# v1_0.net
KiCad netlist of a schematic drawn in EAGLE
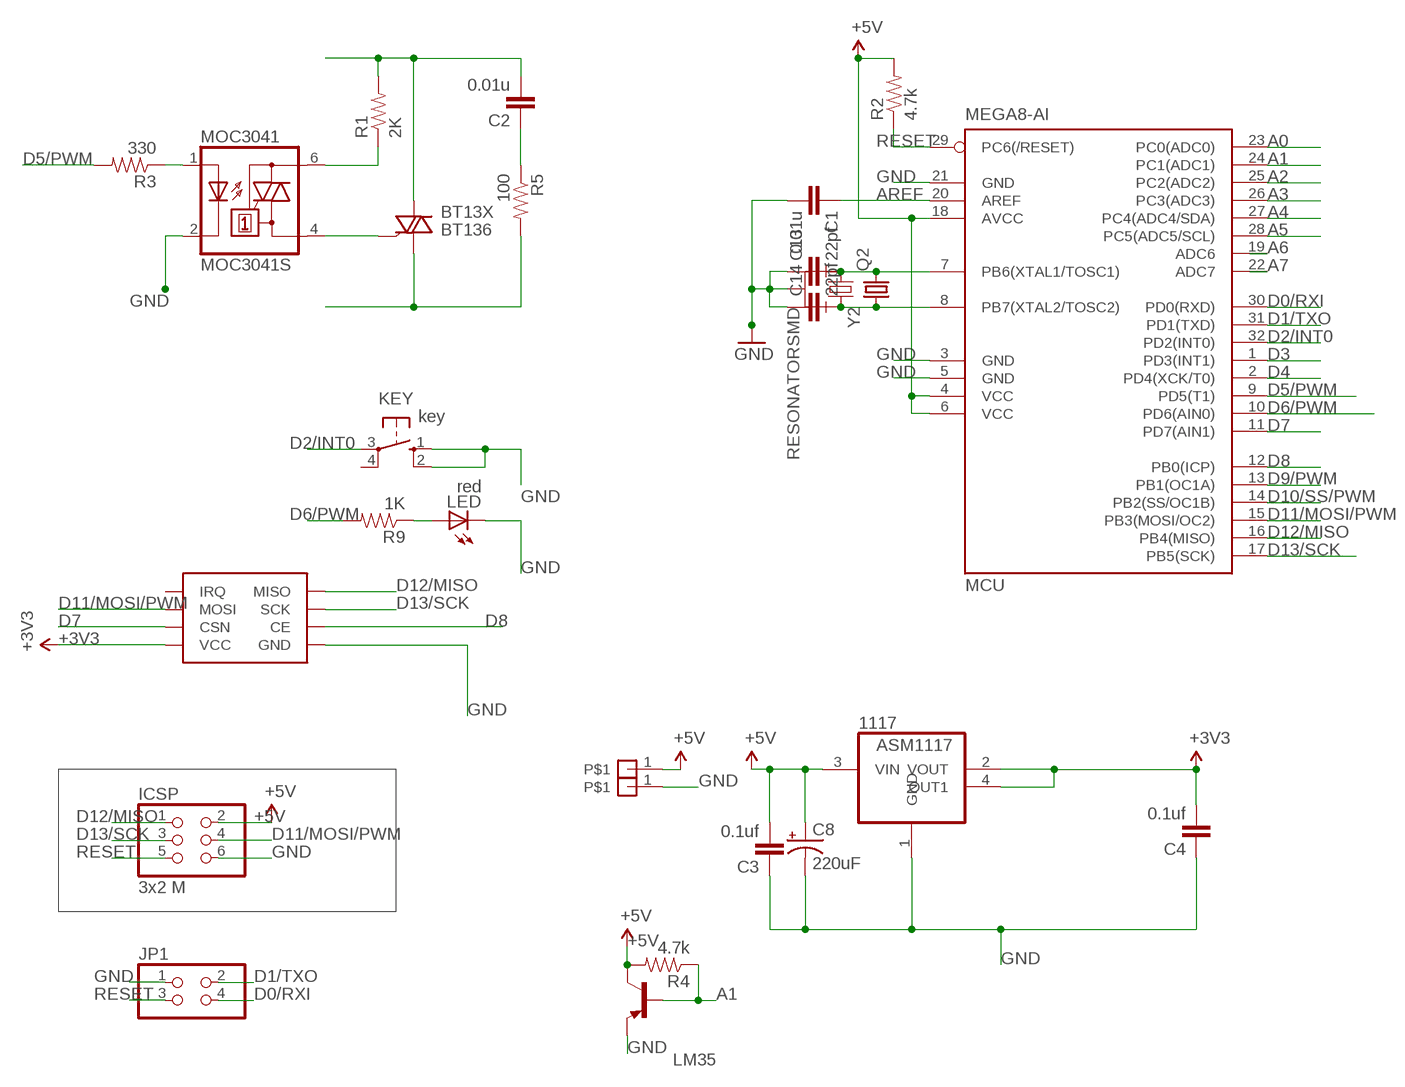
[diagram p0: schematic, sheet 1]

(export (version "E")
  (design (tool "Eeschema 10.0.6"))
  (components
    (comp (ref "1117")
      (value "ASM1117")
      (footprint "eagle-import:SOT223")
      (fields (field (name "MPN") "REG1117"))
      (libsource (lib "eagle-import") (part "ASM1117"))
    )
    (comp (ref "BT13X")
      (value "BT136")
      (footprint "eagle-import:TO252")
      (libsource (lib "eagle-import") (part "BT136"))
    )
    (comp (ref "C1")
      (value "0.01u")
      (footprint "eagle-import:0603-CAP")
      (libsource (lib "eagle-import") (part "MY2_CAP0603-CAP"))
    )
    (comp (ref "C2")
      (value "0.01u")
      (footprint "eagle-import:C050-024X044")
      (libsource (lib "eagle-import") (part "C-EU050-024X044"))
    )
    (comp (ref "C3")
      (value "0.1uf")
      (footprint "eagle-import:0603-CAP")
      (libsource (lib "eagle-import") (part "MY_CAP0603-CAP"))
    )
    (comp (ref "C4")
      (value "0.1uf")
      (footprint "eagle-import:0603-CAP")
      (libsource (lib "eagle-import") (part "MY_CAP0603-CAP"))
    )
    (comp (ref "C8")
      (value "220uF")
      (footprint "eagle-import:EIA3528")
      (libsource (lib "eagle-import") (part "CAP_POL3528"))
    )
    (comp (ref "C13")
      (value "22pf")
      (footprint "eagle-import:0603-CAP")
      (libsource (lib "eagle-import") (part "CAP0603-CAP"))
    )
    (comp (ref "C14")
      (value "22pf")
      (footprint "eagle-import:0603-CAP")
      (libsource (lib "eagle-import") (part "CAP0603-CAP"))
    )
    (comp (ref "ICSP")
      (value "3x2 M")
      (footprint "eagle-import:2X03")
      (libsource (lib "eagle-import") (part "PINHD-2X3"))
    )
    (comp (ref "JP1")
      (value "PINHD-2X2")
      (footprint "eagle-import:2X02")
      (libsource (lib "eagle-import") (part "PINHD-2X2"))
    )
    (comp (ref "KEY")
      (value "key")
      (footprint "eagle-import:B3F-10XX")
      (fields
        (field (name "MPN") "B3F-1000")
        (field (name "MPN_1") "B3F-1000")
        (field (name "OC_FARNELL") "176432")
        (field (name "OC_NEWARK") "36M3542")
      )
      (libsource (lib "eagle-import") (part "10-XX"))
    )
    (comp (ref "LED")
      (value "red")
      (footprint "eagle-import:LED3MM")
      (libsource (lib "eagle-import") (part "LED3MM"))
    )
    (comp (ref "LM35")
      (value "-PNP-TO92-E1")
      (footprint "eagle-import:TO92-E1")
      (libsource (lib "eagle-import") (part "-PNP-TO92-E1"))
    )
    (comp (ref "MCU")
      (value "MEGA8-AI")
      (footprint "eagle-import:TQFP32-08")
      (fields (field (name "MPN") "ATMEGA8-16AU"))
      (libsource (lib "eagle-import") (part "MEGA8-AI"))
    )
    (comp (ref "MOC3041")
      (value "MOC3041S")
      (footprint "eagle-import:DIL6-SMD")
      (fields
        (field (name "MF") "FAIRCHILD SEMICONDUCTOR")
        (field (name "MPN") "MOC3041S-M")
        (field (name "MF_1") "FAIRCHILD SEMICONDUCTOR")
        (field (name "MPN_1") "MOC3041S-M")
        (field (name "OC_NEWARK") "05C2885")
      )
      (libsource (lib "eagle-import") (part "MOC30S41"))
    )
    (comp (ref "Q2")
      (value "CRYSTALHC49S")
      (footprint "eagle-import:HC49_S")
      (libsource (lib "eagle-import") (part "CRYSTALHC49S"))
    )
    (comp (ref "R1")
      (value "2K")
      (footprint "eagle-import:AXIAL-0.3")
      (libsource (lib "eagle-import") (part "MY3_RESISTORPTH1"))
    )
    (comp (ref "R2")
      (value "4.7k")
      (footprint "eagle-import:0603-RES")
      (libsource (lib "eagle-import") (part "RESISTOR0603-RES"))
    )
    (comp (ref "R3")
      (value "330")
      (footprint "eagle-import:0603-RES")
      (libsource (lib "eagle-import") (part "RESISTOR0603-RES"))
    )
    (comp (ref "R4")
      (value "4.7k")
      (footprint "eagle-import:0603-RES")
      (libsource (lib "eagle-import") (part "RESISTOR0603-RES"))
    )
    (comp (ref "R5")
      (value "100")
      (footprint "eagle-import:AXIAL-0.3")
      (libsource (lib "eagle-import") (part "MY3_RESISTORPTH1"))
    )
    (comp (ref "R9")
      (value "1K")
      (footprint "eagle-import:0603-RES")
      (libsource (lib "eagle-import") (part "RESISTOR0603-RES"))
    )
    (comp (ref "U$3")
      (value "PIN1")
      (footprint "eagle-import:PIN1")
      (libsource (lib "eagle-import") (part "PIN1"))
    )
    (comp (ref "U$4")
      (value "PIN1")
      (footprint "eagle-import:PIN1")
      (libsource (lib "eagle-import") (part "PIN1"))
    )
    (comp (ref "U$6")
      (value "NRF")
      (footprint "eagle-import:NRF")
      (libsource (lib "eagle-import") (part "NRF"))
    )
    (comp (ref "Y2")
      (value "RESONATORSMD")
      (footprint "eagle-import:RESONATOR-SMD")
      (libsource (lib "eagle-import") (part "RESONATORSMD"))
    )
  )
  (nets
    (net (code "1") (name "+3V3") (class "Default")
      (node (ref "1117") (pin "2") (pinfunction "VOUT_2") (pintype "output"))
      (node (ref "1117") (pin "4") (pinfunction "OUT1_4") (pintype "bidirectional"))
      (node (ref "C4") (pin "2") (pinfunction "2_2") (pintype "passive"))
      (node (ref "U$6") (pin "P$2") (pinfunction "VCC_P$2") (pintype "bidirectional"))
    )
    (net (code "2") (name "+5V") (class "Default")
      (node (ref "1117") (pin "3") (pinfunction "VIN_3") (pintype "input"))
      (node (ref "C3") (pin "2") (pinfunction "2_2") (pintype "passive"))
      (node (ref "C8") (pin "A") (pinfunction "+_A") (pintype "passive"))
      (node (ref "ICSP") (pin "2") (pinfunction "2_2") (pintype "passive"))
      (node (ref "LM35") (pin "1") (pinfunction "C_1") (pintype "passive"))
      (node (ref "MCU") (pin "18") (pinfunction "AVCC_18") (pintype "power_in"))
      (node (ref "MCU") (pin "4") (pinfunction "VCC_4") (pintype "power_in"))
      (node (ref "MCU") (pin "6") (pinfunction "VCC_6") (pintype "power_in"))
      (node (ref "R2") (pin "2") (pinfunction "2_2") (pintype "passive"))
      (node (ref "R4") (pin "2") (pinfunction "2_2") (pintype "passive"))
      (node (ref "U$3") (pin "1") (pinfunction "P$1_1") (pintype "bidirectional"))
    )
    (net (code "3") (name "/A0") (class "Default")
      (node (ref "MCU") (pin "23") (pinfunction "PC0(ADC0)_23") (pintype "bidirectional"))
    )
    (net (code "4") (name "/A1") (class "Default")
      (node (ref "LM35") (pin "2") (pinfunction "B_2") (pintype "passive"))
      (node (ref "MCU") (pin "24") (pinfunction "PC1(ADC1)_24") (pintype "bidirectional"))
      (node (ref "R4") (pin "1") (pinfunction "1_1") (pintype "passive"))
    )
    (net (code "5") (name "/A2") (class "Default")
      (node (ref "MCU") (pin "25") (pinfunction "PC2(ADC2)_25") (pintype "bidirectional"))
    )
    (net (code "6") (name "/A3") (class "Default")
      (node (ref "MCU") (pin "26") (pinfunction "PC3(ADC3)_26") (pintype "bidirectional"))
    )
    (net (code "7") (name "/A4") (class "Default")
      (node (ref "MCU") (pin "27") (pinfunction "PC4(ADC4/SDA)_27") (pintype "bidirectional"))
    )
    (net (code "8") (name "/A5") (class "Default")
      (node (ref "MCU") (pin "28") (pinfunction "PC5(ADC5/SCL)_28") (pintype "bidirectional"))
    )
    (net (code "9") (name "/A6") (class "Default")
      (node (ref "MCU") (pin "19") (pinfunction "ADC6_19") (pintype "bidirectional"))
    )
    (net (code "10") (name "/A7") (class "Default")
      (node (ref "MCU") (pin "22") (pinfunction "ADC7_22") (pintype "bidirectional"))
    )
    (net (code "11") (name "/AREF") (class "Default")
      (node (ref "C1") (pin "1") (pinfunction "1_1") (pintype "passive"))
      (node (ref "MCU") (pin "20") (pinfunction "AREF_20") (pintype "passive"))
    )
    (net (code "12") (name "/D0{slash}RXI") (class "Default")
      (node (ref "JP1") (pin "4") (pinfunction "4_4") (pintype "passive"))
      (node (ref "MCU") (pin "30") (pinfunction "PD0(RXD)_30") (pintype "bidirectional"))
    )
    (net (code "13") (name "/D1{slash}TXO") (class "Default")
      (node (ref "JP1") (pin "2") (pinfunction "2_2") (pintype "passive"))
      (node (ref "MCU") (pin "31") (pinfunction "PD1(TXD)_31") (pintype "bidirectional"))
    )
    (net (code "14") (name "/D2{slash}INT0") (class "Default")
      (node (ref "KEY") (pin "3") (pinfunction "P_3") (pintype "passive"))
      (node (ref "MCU") (pin "32") (pinfunction "PD2(INT0)_32") (pintype "bidirectional"))
    )
    (net (code "15") (name "/D3") (class "Default")
      (node (ref "MCU") (pin "1") (pinfunction "PD3(INT1)_1") (pintype "bidirectional"))
    )
    (net (code "16") (name "/D4") (class "Default")
      (node (ref "MCU") (pin "2") (pinfunction "PD4(XCK/T0)_2") (pintype "bidirectional"))
    )
    (net (code "17") (name "/D5{slash}PWM") (class "Default")
      (node (ref "MCU") (pin "9") (pinfunction "PD5(T1)_9") (pintype "bidirectional"))
      (node (ref "R3") (pin "2") (pinfunction "2_2") (pintype "passive"))
    )
    (net (code "18") (name "/D6{slash}PWM") (class "Default")
      (node (ref "MCU") (pin "10") (pinfunction "PD6(AIN0)_10") (pintype "bidirectional"))
      (node (ref "R9") (pin "2") (pinfunction "2_2") (pintype "passive"))
    )
    (net (code "19") (name "/D7") (class "Default")
      (node (ref "MCU") (pin "11") (pinfunction "PD7(AIN1)_11") (pintype "bidirectional"))
      (node (ref "U$6") (pin "P$4") (pinfunction "CSN_P$4") (pintype "bidirectional"))
    )
    (net (code "20") (name "/D8") (class "Default")
      (node (ref "MCU") (pin "12") (pinfunction "PB0(ICP)_12") (pintype "bidirectional"))
      (node (ref "U$6") (pin "P$3") (pinfunction "CE_P$3") (pintype "bidirectional"))
    )
    (net (code "21") (name "/D9{slash}PWM") (class "Default")
      (node (ref "MCU") (pin "13") (pinfunction "PB1(OC1A)_13") (pintype "bidirectional"))
    )
    (net (code "22") (name "/D10{slash}SS{slash}PWM") (class "Default")
      (node (ref "MCU") (pin "14") (pinfunction "PB2(SS/OC1B)_14") (pintype "bidirectional"))
    )
    (net (code "23") (name "/D11{slash}MOSI{slash}PWM") (class "Default")
      (node (ref "ICSP") (pin "4") (pinfunction "4_4") (pintype "passive"))
      (node (ref "MCU") (pin "15") (pinfunction "PB3(MOSI/OC2)_15") (pintype "bidirectional"))
      (node (ref "U$6") (pin "P$6") (pinfunction "MOSI_P$6") (pintype "bidirectional"))
    )
    (net (code "24") (name "/D12{slash}MISO") (class "Default")
      (node (ref "ICSP") (pin "1") (pinfunction "1_1") (pintype "passive"))
      (node (ref "MCU") (pin "16") (pinfunction "PB4(MISO)_16") (pintype "bidirectional"))
      (node (ref "U$6") (pin "P$7") (pinfunction "MISO_P$7") (pintype "bidirectional"))
    )
    (net (code "25") (name "/D13{slash}SCK") (class "Default")
      (node (ref "ICSP") (pin "3") (pinfunction "3_3") (pintype "passive"))
      (node (ref "MCU") (pin "17") (pinfunction "PB5(SCK)_17") (pintype "bidirectional"))
      (node (ref "U$6") (pin "P$5") (pinfunction "SCK_P$5") (pintype "bidirectional"))
    )
    (net (code "26") (name "/RESET") (class "Default")
      (node (ref "ICSP") (pin "5") (pinfunction "5_5") (pintype "passive"))
      (node (ref "JP1") (pin "3") (pinfunction "3_3") (pintype "passive"))
      (node (ref "MCU") (pin "29") (pinfunction "PC6(/RESET)_29") (pintype "bidirectional"))
      (node (ref "R2") (pin "1") (pinfunction "1_1") (pintype "passive"))
    )
    (net (code "27") (name "GND") (class "Default")
      (node (ref "1117") (pin "1") (pinfunction "GND_1") (pintype "power_in"))
      (node (ref "C1") (pin "2") (pinfunction "2_2") (pintype "passive"))
      (node (ref "C13") (pin "1") (pinfunction "1_1") (pintype "passive"))
      (node (ref "C14") (pin "1") (pinfunction "1_1") (pintype "passive"))
      (node (ref "C3") (pin "1") (pinfunction "1_1") (pintype "passive"))
      (node (ref "C4") (pin "1") (pinfunction "1_1") (pintype "passive"))
      (node (ref "C8") (pin "C") (pinfunction "-_C") (pintype "passive"))
      (node (ref "ICSP") (pin "6") (pinfunction "6_6") (pintype "passive"))
      (node (ref "JP1") (pin "1") (pinfunction "1_1") (pintype "passive"))
      (node (ref "KEY") (pin "1") (pinfunction "S_1") (pintype "passive"))
      (node (ref "KEY") (pin "2") (pinfunction "S1_2") (pintype "passive"))
      (node (ref "LED") (pin "K") (pinfunction "C_K") (pintype "passive"))
      (node (ref "LM35") (pin "3") (pinfunction "E_3") (pintype "passive"))
      (node (ref "MCU") (pin "21") (pinfunction "GND_21") (pintype "power_in"))
      (node (ref "MCU") (pin "3") (pinfunction "GND_3") (pintype "power_in"))
      (node (ref "MCU") (pin "5") (pinfunction "GND_5") (pintype "power_in"))
      (node (ref "MOC3041") (pin "2") (pinfunction "C_2") (pintype "passive"))
      (node (ref "U$4") (pin "1") (pinfunction "P$1_1") (pintype "bidirectional"))
      (node (ref "U$6") (pin "P$1") (pinfunction "GND_P$1") (pintype "bidirectional"))
      (node (ref "Y2") (pin "2") (pinfunction "2_2") (pintype "passive"))
    )
    (net (code "28") (name "Net-(BT13X-A1)") (class "Default")
      (node (ref "BT13X") (pin "1") (pinfunction "A1_1") (pintype "passive"))
      (node (ref "R5") (pin "P$2") (pinfunction "2_P$2") (pintype "passive"))
    )
    (net (code "29") (name "Net-(BT13X-A2)") (class "Default")
      (node (ref "BT13X") (pin "3") (pinfunction "A2_3") (pintype "passive"))
      (node (ref "C2") (pin "2") (pinfunction "2_2") (pintype "passive"))
      (node (ref "R1") (pin "P$2") (pinfunction "2_P$2") (pintype "passive"))
    )
    (net (code "30") (name "Net-(BT13X-G)") (class "Default")
      (node (ref "BT13X") (pin "2") (pinfunction "G_2") (pintype "passive"))
      (node (ref "MOC3041") (pin "4") (pinfunction "A1_4") (pintype "passive"))
    )
    (net (code "31") (name "Net-(LED-PadA)") (class "Default")
      (node (ref "LED") (pin "A") (pinfunction "A_A") (pintype "passive"))
      (node (ref "R9") (pin "1") (pinfunction "1_1") (pintype "passive"))
    )
    (net (code "32") (name "Net-(MCU-PB6(XTAL1{slash}TOSC1))") (class "Default")
      (node (ref "C13") (pin "2") (pinfunction "2_2") (pintype "passive"))
      (node (ref "MCU") (pin "7") (pinfunction "PB6(XTAL1/TOSC1)_7") (pintype "bidirectional"))
      (node (ref "Q2") (pin "2") (pinfunction "2_2") (pintype "passive"))
      (node (ref "Y2") (pin "1") (pinfunction "1_1") (pintype "passive"))
    )
    (net (code "33") (name "Net-(MCU-PB7(XTAL2{slash}TOSC2))") (class "Default")
      (node (ref "C14") (pin "2") (pinfunction "2_2") (pintype "passive"))
      (node (ref "MCU") (pin "8") (pinfunction "PB7(XTAL2/TOSC2)_8") (pintype "bidirectional"))
      (node (ref "Q2") (pin "1") (pinfunction "1_1") (pintype "passive"))
      (node (ref "Y2") (pin "3") (pinfunction "3_3") (pintype "passive"))
    )
    (net (code "34") (name "Net-(MOC3041-A)") (class "Default")
      (node (ref "MOC3041") (pin "1") (pinfunction "A_1") (pintype "passive"))
      (node (ref "R3") (pin "1") (pinfunction "1_1") (pintype "passive"))
    )
    (net (code "35") (name "Net-(MOC3041-A2)") (class "Default")
      (node (ref "MOC3041") (pin "6") (pinfunction "A2_6") (pintype "passive"))
      (node (ref "R1") (pin "P$1") (pinfunction "1_P$1") (pintype "passive"))
    )
    (net (code "36") (name "Net-(R5-1)") (class "Default")
      (node (ref "C2") (pin "1") (pinfunction "1_1") (pintype "passive"))
      (node (ref "R5") (pin "P$1") (pinfunction "1_P$1") (pintype "passive"))
    )
    (net (code "37") (name "unconnected-(KEY-P1-Pad4)") (class "Default")
      (node (ref "KEY") (pin "4") (pinfunction "P1_4") (pintype "passive"))
    )
    (net (code "38") (name "unconnected-(U$6-IRQ-PadP$8)") (class "Default")
      (node (ref "U$6") (pin "P$8") (pinfunction "IRQ_P$8") (pintype "bidirectional"))
    )
  )
)
